# vn210-breakout.net
KiCad netlist of a schematic drawn in EAGLE
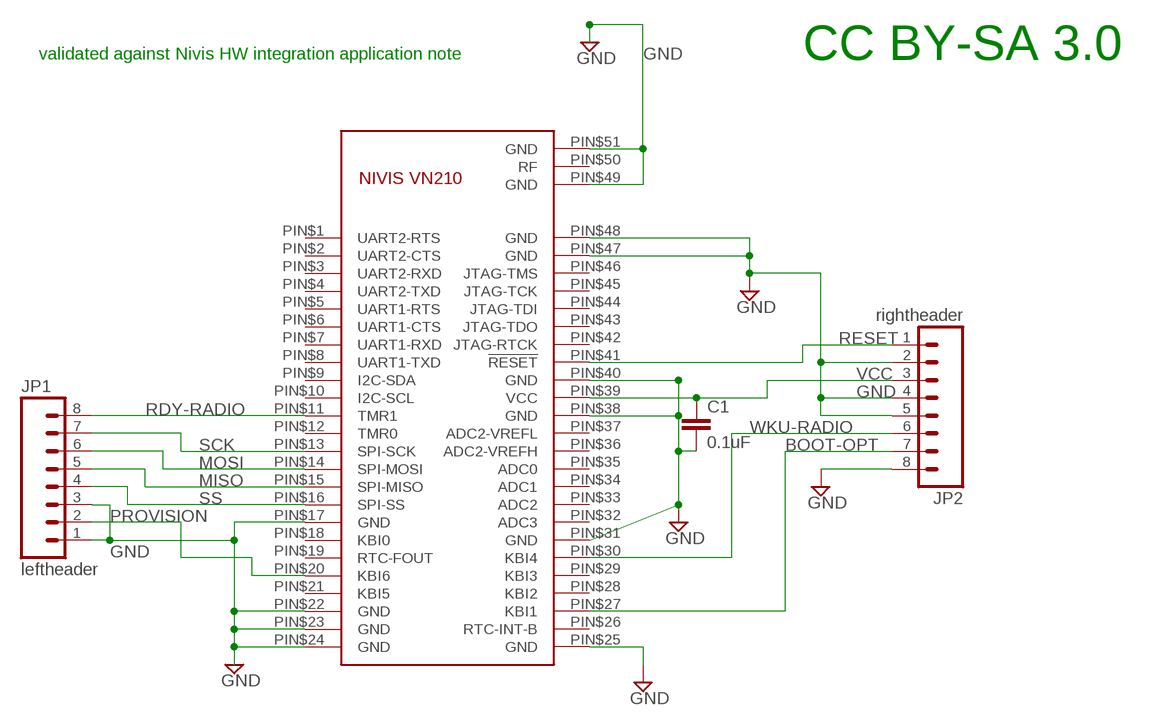
[diagram p0: schematic, sheet 1]

(export (version "E")
  (design (tool "Eeschema 10.0.6"))
  (components
    (comp (ref "C1")
      (value "0.1uF")
      (footprint "eagle-import:C1206")
      (libsource (lib "eagle-import") (part "C-EUC1206"))
    )
    (comp (ref "JP1")
      (value "leftheader")
      (footprint "eagle-import:1X08")
      (libsource (lib "eagle-import") (part "M081X08"))
    )
    (comp (ref "JP2")
      (value "rightheader")
      (footprint "eagle-import:1X08")
      (libsource (lib "eagle-import") (part "M081X08"))
    )
    (comp (ref "U$1")
      (value "VN210")
      (footprint "eagle-import:VN210")
      (libsource (lib "eagle-import") (part "VN210"))
    )
  )
  (nets
    (net (code "1") (name "/BOOT-OPT") (class "Default")
      (node (ref "JP2") (pin "7") (pinfunction "7_7") (pintype "passive"))
      (node (ref "U$1") (pin "PIN$27") (pinfunction "KBI1_PIN$27") (pintype "input"))
    )
    (net (code "2") (name "/MISO") (class "Default")
      (node (ref "JP1") (pin "5") (pinfunction "5_5") (pintype "passive"))
      (node (ref "U$1") (pin "PIN$15") (pinfunction "SPI-MISO_PIN$15") (pintype "input"))
    )
    (net (code "3") (name "/MOSI") (class "Default")
      (node (ref "JP1") (pin "6") (pinfunction "6_6") (pintype "passive"))
      (node (ref "U$1") (pin "PIN$14") (pinfunction "SPI-MOSI_PIN$14") (pintype "output"))
    )
    (net (code "4") (name "/PROVISION") (class "Default")
      (node (ref "JP1") (pin "2") (pinfunction "2_2") (pintype "passive"))
      (node (ref "U$1") (pin "PIN$20") (pinfunction "KBI6_PIN$20") (pintype "input"))
    )
    (net (code "5") (name "/RDY-RADIO") (class "Default")
      (node (ref "JP1") (pin "8") (pinfunction "8_8") (pintype "passive"))
      (node (ref "U$1") (pin "PIN$11") (pinfunction "TMR1_PIN$11") (pintype "output"))
    )
    (net (code "6") (name "/RESET") (class "Default")
      (node (ref "JP2") (pin "1") (pinfunction "1_1") (pintype "passive"))
      (node (ref "U$1") (pin "PIN$41") (pinfunction "~{RESET}_PIN$41") (pintype "input"))
    )
    (net (code "7") (name "/SCK") (class "Default")
      (node (ref "JP1") (pin "7") (pinfunction "7_7") (pintype "passive"))
      (node (ref "U$1") (pin "PIN$13") (pinfunction "SPI-SCK_PIN$13") (pintype "output"))
    )
    (net (code "8") (name "/SS") (class "Default")
      (node (ref "JP1") (pin "4") (pinfunction "4_4") (pintype "passive"))
      (node (ref "U$1") (pin "PIN$16") (pinfunction "SPI-SS_PIN$16") (pintype "output"))
    )
    (net (code "9") (name "/VCC") (class "Default")
      (node (ref "C1") (pin "1") (pinfunction "1_1") (pintype "passive"))
      (node (ref "JP2") (pin "3") (pinfunction "3_3") (pintype "passive"))
      (node (ref "U$1") (pin "PIN$39") (pinfunction "VCC_PIN$39") (pintype "power_in"))
    )
    (net (code "10") (name "/WKU-RADIO") (class "Default")
      (node (ref "JP2") (pin "6") (pinfunction "6_6") (pintype "passive"))
      (node (ref "U$1") (pin "PIN$30") (pinfunction "KBI4_PIN$30") (pintype "input"))
    )
    (net (code "11") (name "GND") (class "Default")
      (node (ref "C1") (pin "2") (pinfunction "2_2") (pintype "passive"))
      (node (ref "JP1") (pin "1") (pinfunction "1_1") (pintype "passive"))
      (node (ref "JP1") (pin "3") (pinfunction "3_3") (pintype "passive"))
      (node (ref "JP2") (pin "2") (pinfunction "2_2") (pintype "passive"))
      (node (ref "JP2") (pin "4") (pinfunction "4_4") (pintype "passive"))
      (node (ref "JP2") (pin "5") (pinfunction "5_5") (pintype "passive"))
      (node (ref "JP2") (pin "8") (pinfunction "8_8") (pintype "passive"))
      (node (ref "U$1") (pin "PIN$17") (pinfunction "GND_PIN$17") (pintype "power_in"))
      (node (ref "U$1") (pin "PIN$22") (pinfunction "GND_PIN$22") (pintype "power_in"))
      (node (ref "U$1") (pin "PIN$23") (pinfunction "GND_PIN$23") (pintype "power_in"))
      (node (ref "U$1") (pin "PIN$24") (pinfunction "GND_PIN$24") (pintype "power_in"))
      (node (ref "U$1") (pin "PIN$25") (pinfunction "GND_PIN$25") (pintype "power_in"))
      (node (ref "U$1") (pin "PIN$31") (pinfunction "GND_PIN$31") (pintype "power_in"))
      (node (ref "U$1") (pin "PIN$38") (pinfunction "GND_PIN$38") (pintype "power_in"))
      (node (ref "U$1") (pin "PIN$40") (pinfunction "GND_PIN$40") (pintype "power_in"))
      (node (ref "U$1") (pin "PIN$47") (pinfunction "GND_PIN$47") (pintype "power_in"))
      (node (ref "U$1") (pin "PIN$48") (pinfunction "GND_PIN$48") (pintype "power_in"))
      (node (ref "U$1") (pin "PIN$49") (pinfunction "GND_PIN$49") (pintype "power_in"))
      (node (ref "U$1") (pin "PIN$51") (pinfunction "GND_PIN$51") (pintype "power_in"))
    )
    (net (code "12") (name "unconnected-(U$1-ADC0-PadPIN$35)") (class "Default")
      (node (ref "U$1") (pin "PIN$35") (pinfunction "ADC0_PIN$35") (pintype "no_connect"))
    )
    (net (code "13") (name "unconnected-(U$1-ADC1-PadPIN$34)") (class "Default")
      (node (ref "U$1") (pin "PIN$34") (pinfunction "ADC1_PIN$34") (pintype "output"))
    )
    (net (code "14") (name "unconnected-(U$1-ADC2-PadPIN$33)") (class "Default")
      (node (ref "U$1") (pin "PIN$33") (pinfunction "ADC2_PIN$33") (pintype "no_connect"))
    )
    (net (code "15") (name "unconnected-(U$1-ADC2-VREFH-PadPIN$36)") (class "Default")
      (node (ref "U$1") (pin "PIN$36") (pinfunction "ADC2-VREFH_PIN$36") (pintype "no_connect"))
    )
    (net (code "16") (name "unconnected-(U$1-ADC2-VREFL-PadPIN$37)") (class "Default")
      (node (ref "U$1") (pin "PIN$37") (pinfunction "ADC2-VREFL_PIN$37") (pintype "no_connect"))
    )
    (net (code "17") (name "unconnected-(U$1-ADC3-PadPIN$32)") (class "Default")
      (node (ref "U$1") (pin "PIN$32") (pinfunction "ADC3_PIN$32") (pintype "no_connect"))
    )
    (net (code "18") (name "unconnected-(U$1-I2C-SCL-PadPIN$10)") (class "Default")
      (node (ref "U$1") (pin "PIN$10") (pinfunction "I2C-SCL_PIN$10") (pintype "no_connect"))
    )
    (net (code "19") (name "unconnected-(U$1-I2C-SDA-PadPIN$9)") (class "Default")
      (node (ref "U$1") (pin "PIN$9") (pinfunction "I2C-SDA_PIN$9") (pintype "no_connect"))
    )
    (net (code "20") (name "unconnected-(U$1-JTAG-RTCK-PadPIN$42)") (class "Default")
      (node (ref "U$1") (pin "PIN$42") (pinfunction "JTAG-RTCK_PIN$42") (pintype "output"))
    )
    (net (code "21") (name "unconnected-(U$1-JTAG-TCK-PadPIN$45)") (class "Default")
      (node (ref "U$1") (pin "PIN$45") (pinfunction "JTAG-TCK_PIN$45") (pintype "input"))
    )
    (net (code "22") (name "unconnected-(U$1-JTAG-TDI-PadPIN$44)") (class "Default")
      (node (ref "U$1") (pin "PIN$44") (pinfunction "JTAG-TDI_PIN$44") (pintype "input"))
    )
    (net (code "23") (name "unconnected-(U$1-JTAG-TDO-PadPIN$43)") (class "Default")
      (node (ref "U$1") (pin "PIN$43") (pinfunction "JTAG-TDO_PIN$43") (pintype "input"))
    )
    (net (code "24") (name "unconnected-(U$1-JTAG-TMS-PadPIN$46)") (class "Default")
      (node (ref "U$1") (pin "PIN$46") (pinfunction "JTAG-TMS_PIN$46") (pintype "input"))
    )
    (net (code "25") (name "unconnected-(U$1-KBI0-PadPIN$18)") (class "Default")
      (node (ref "U$1") (pin "PIN$18") (pinfunction "KBI0_PIN$18") (pintype "no_connect"))
    )
    (net (code "26") (name "unconnected-(U$1-KBI2-PadPIN$28)") (class "Default")
      (node (ref "U$1") (pin "PIN$28") (pinfunction "KBI2_PIN$28") (pintype "no_connect"))
    )
    (net (code "27") (name "unconnected-(U$1-KBI3-PadPIN$29)") (class "Default")
      (node (ref "U$1") (pin "PIN$29") (pinfunction "KBI3_PIN$29") (pintype "no_connect"))
    )
    (net (code "28") (name "unconnected-(U$1-KBI5-PadPIN$21)") (class "Default")
      (node (ref "U$1") (pin "PIN$21") (pinfunction "KBI5_PIN$21") (pintype "no_connect"))
    )
    (net (code "29") (name "unconnected-(U$1-RF-PadPIN$50)") (class "Default")
      (node (ref "U$1") (pin "PIN$50") (pinfunction "RF_PIN$50") (pintype "bidirectional"))
    )
    (net (code "30") (name "unconnected-(U$1-RTC-FOUT-PadPIN$19)") (class "Default")
      (node (ref "U$1") (pin "PIN$19") (pinfunction "RTC-FOUT_PIN$19") (pintype "output"))
    )
    (net (code "31") (name "unconnected-(U$1-RTC-INT-B-PadPIN$26)") (class "Default")
      (node (ref "U$1") (pin "PIN$26") (pinfunction "RTC-INT-B_PIN$26") (pintype "no_connect"))
    )
    (net (code "32") (name "unconnected-(U$1-TMR0-PadPIN$12)") (class "Default")
      (node (ref "U$1") (pin "PIN$12") (pinfunction "TMR0_PIN$12") (pintype "no_connect"))
    )
    (net (code "33") (name "unconnected-(U$1-UART1-CTS-PadPIN$6)") (class "Default")
      (node (ref "U$1") (pin "PIN$6") (pinfunction "UART1-CTS_PIN$6") (pintype "no_connect"))
    )
    (net (code "34") (name "unconnected-(U$1-UART1-RTS-PadPIN$5)") (class "Default")
      (node (ref "U$1") (pin "PIN$5") (pinfunction "UART1-RTS_PIN$5") (pintype "no_connect"))
    )
    (net (code "35") (name "unconnected-(U$1-UART1-RXD-PadPIN$7)") (class "Default")
      (node (ref "U$1") (pin "PIN$7") (pinfunction "UART1-RXD_PIN$7") (pintype "input"))
    )
    (net (code "36") (name "unconnected-(U$1-UART1-TXD-PadPIN$8)") (class "Default")
      (node (ref "U$1") (pin "PIN$8") (pinfunction "UART1-TXD_PIN$8") (pintype "output"))
    )
    (net (code "37") (name "unconnected-(U$1-UART2-CTS-PadPIN$2)") (class "Default")
      (node (ref "U$1") (pin "PIN$2") (pinfunction "UART2-CTS_PIN$2") (pintype "output"))
    )
    (net (code "38") (name "unconnected-(U$1-UART2-RTS-PadPIN$1)") (class "Default")
      (node (ref "U$1") (pin "PIN$1") (pinfunction "UART2-RTS_PIN$1") (pintype "input"))
    )
    (net (code "39") (name "unconnected-(U$1-UART2-RXD-PadPIN$3)") (class "Default")
      (node (ref "U$1") (pin "PIN$3") (pinfunction "UART2-RXD_PIN$3") (pintype "input"))
    )
    (net (code "40") (name "unconnected-(U$1-UART2-TXD-PadPIN$4)") (class "Default")
      (node (ref "U$1") (pin "PIN$4") (pinfunction "UART2-TXD_PIN$4") (pintype "output"))
    )
  )
)
